# STORAGE.net
KiCad netlist of a schematic drawn in Altium Designer
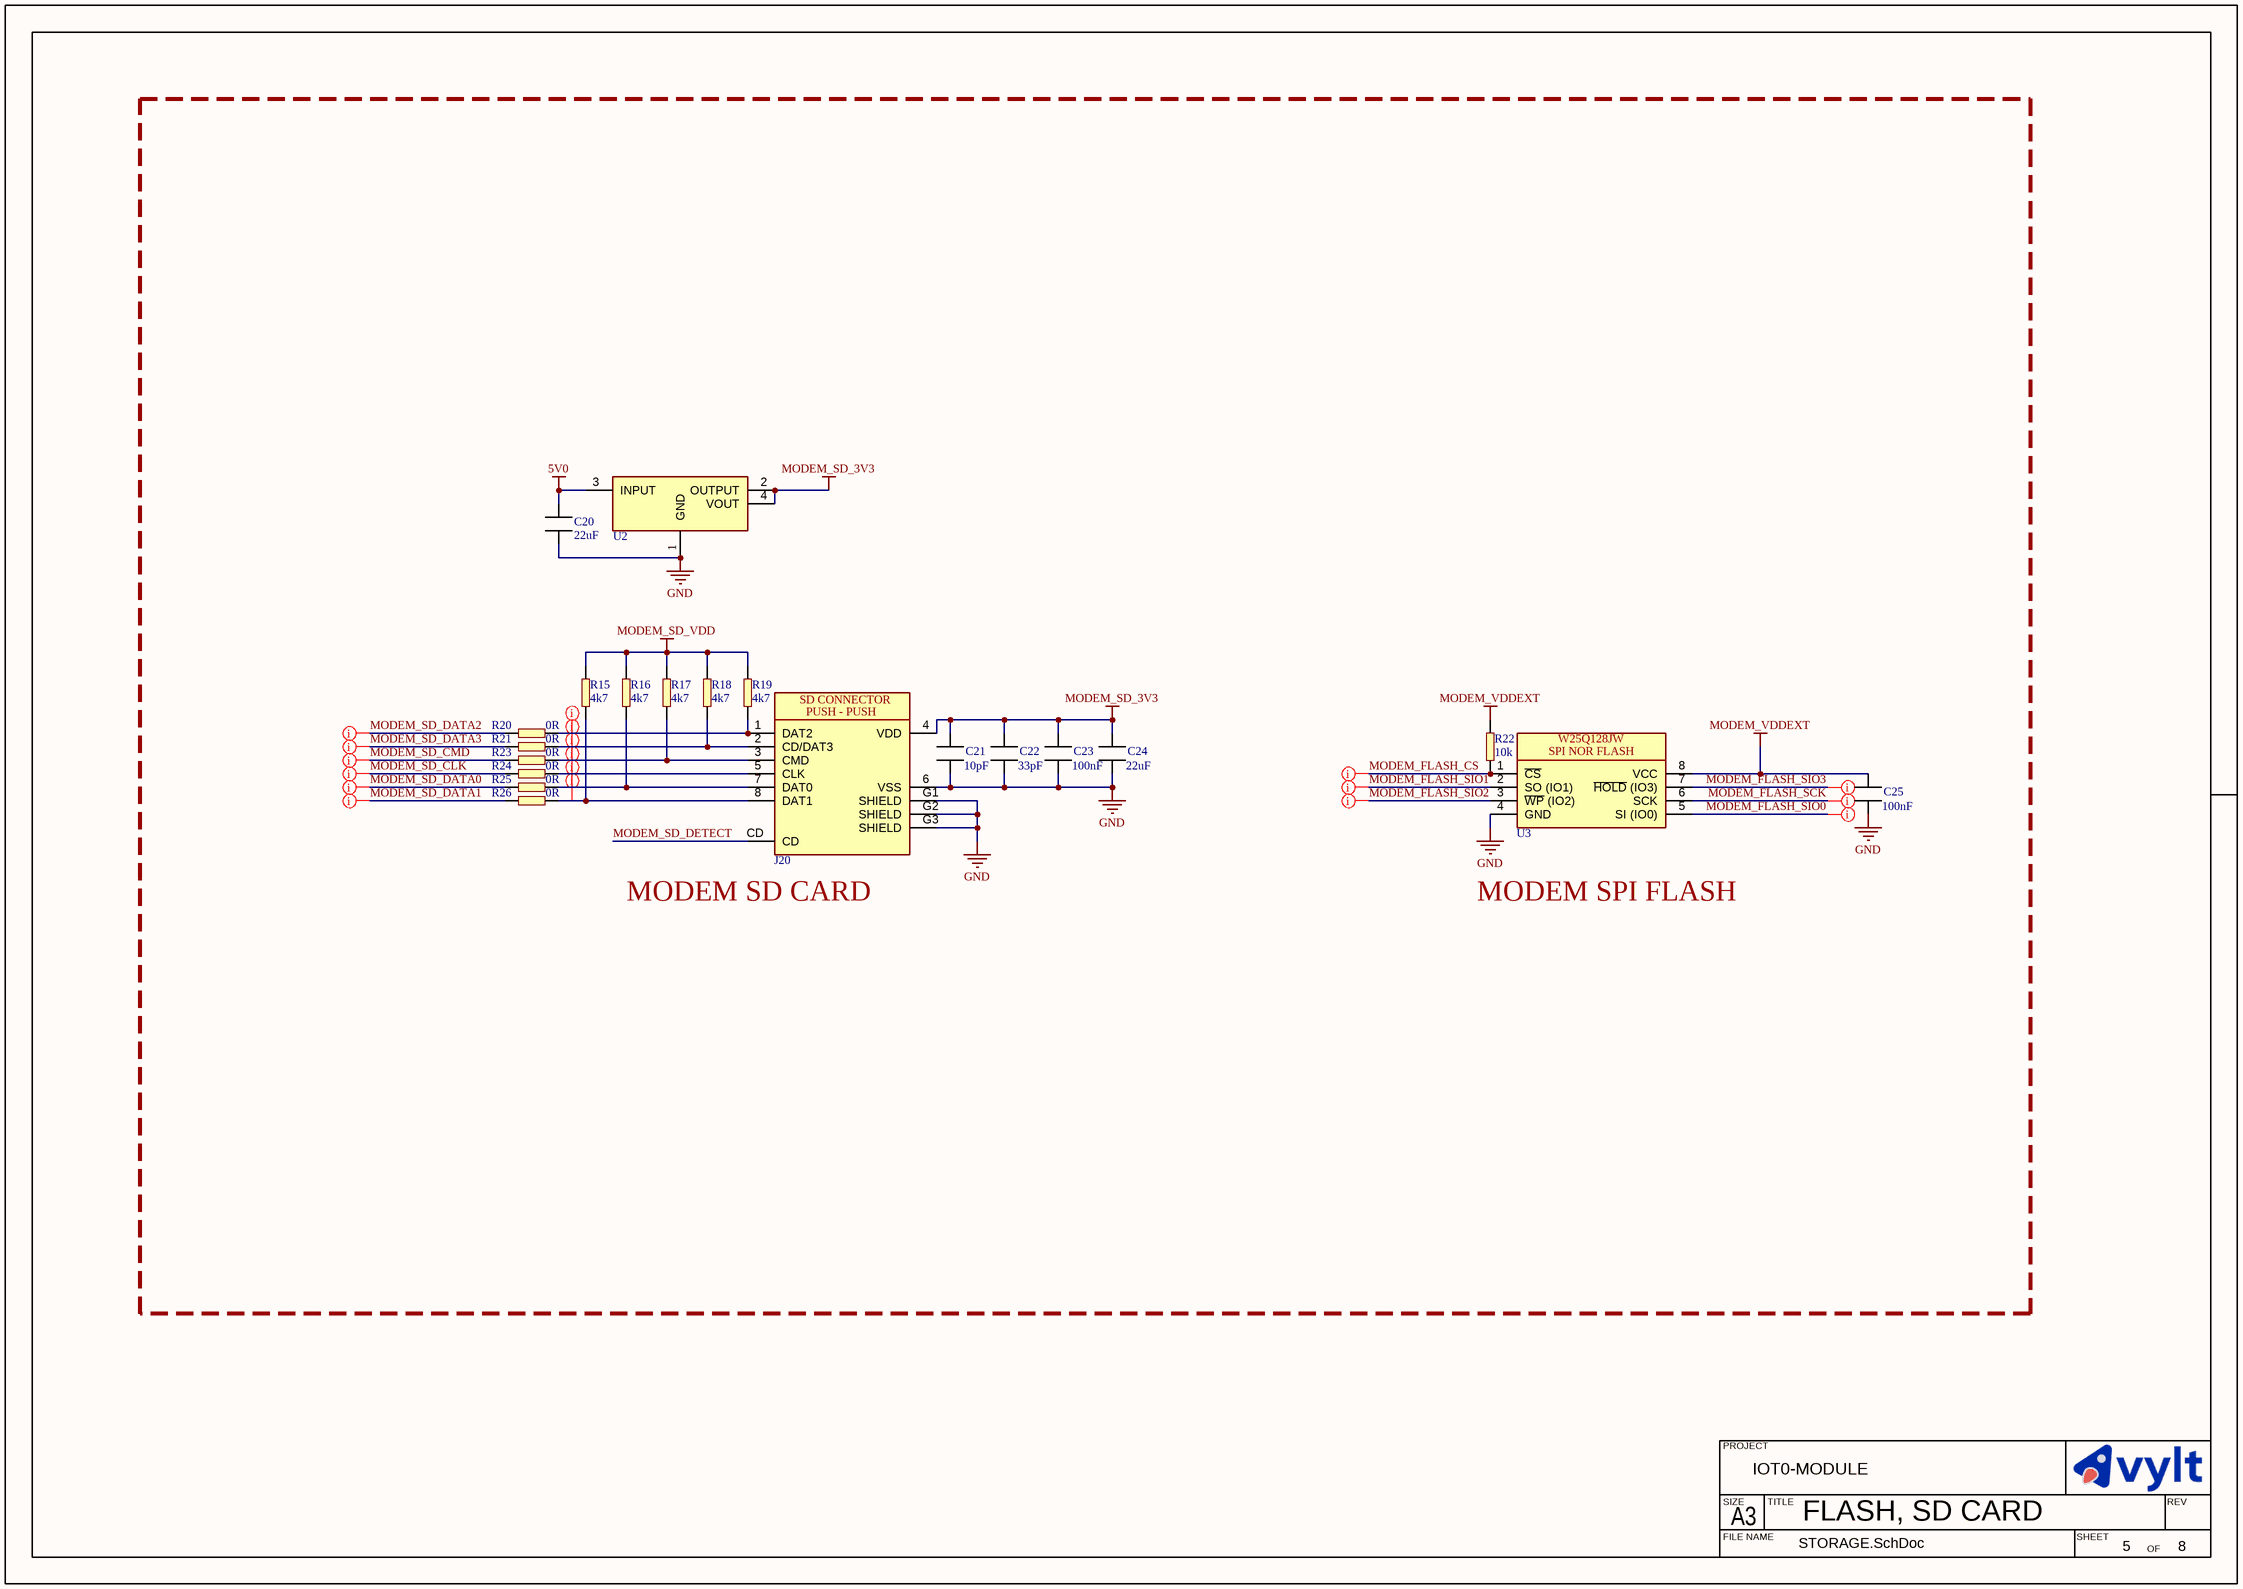
[diagram p0: STORAGE.SchDoc]

(export (version "E")
  (design (tool "Eeschema 10.0.6"))
  (components
    (comp (ref "C20")
      (value "22uF")
      (footprint "CAPC2012X13L")
      (description "Chip Capacitor, 2-Leads, Body 2.00x1.25mm, IPC High Density")
      (fields (field (name "Comment") "MLCC_0805"))
      (libsource (lib "Capacitor") (part "MLCC_0805"))
    )
    (comp (ref "C21")
      (value "10pF")
      (footprint "CAPC2012X13L")
      (description "Chip Capacitor, 2-Leads, Body 2.00x1.25mm, IPC High Density")
      (fields (field (name "Comment") "MLCC_0805"))
      (libsource (lib "Capacitor") (part "MLCC_0805"))
    )
    (comp (ref "C22")
      (value "33pF")
      (footprint "CAPC2012X13L")
      (description "Chip Capacitor, 2-Leads, Body 2.00x1.25mm, IPC High Density")
      (fields (field (name "Comment") "MLCC_0805"))
      (libsource (lib "Capacitor") (part "MLCC_0805"))
    )
    (comp (ref "C23")
      (value "100nF")
      (footprint "CAPC2012X13L")
      (description "Chip Capacitor, 2-Leads, Body 2.00x1.25mm, IPC High Density")
      (fields (field (name "Comment") "MLCC_0805"))
      (libsource (lib "Capacitor") (part "MLCC_0805"))
    )
    (comp (ref "C24")
      (value "22uF")
      (footprint "CAPC2012X13L")
      (description "Chip Capacitor, 2-Leads, Body 2.00x1.25mm, IPC High Density")
      (fields (field (name "Comment") "MLCC_0805"))
      (libsource (lib "Capacitor") (part "MLCC_0805"))
    )
    (comp (ref "C25")
      (value "100nF")
      (footprint "CAPC2012X13L")
      (description "Chip Capacitor, 2-Leads, Body 2.00x1.25mm, IPC High Density")
      (fields (field (name "Comment") "MLCC_0805"))
      (libsource (lib "Capacitor") (part "MLCC_0805"))
    )
    (comp (ref "J20")
      (value "GTFP084")
      (footprint "GTFP084")
      (description "9 (8 + 1) Position Card Connector Secure Digital - microSD™ Surface Mount, Right Angle Gold")
      (libsource (lib "Connectors") (part "GTFP084"))
    )
    (comp (ref "R15")
      (value "4k7")
      (footprint "RES_0603")
      (description "RES_0603")
      (fields (field (name "Comment") "ERP_101-1"))
      (libsource (lib "Resistor") (part "RES_0603"))
    )
    (comp (ref "R16")
      (value "4k7")
      (footprint "RES_0603")
      (description "RES_0603")
      (fields (field (name "Comment") "ERP_101-1"))
      (libsource (lib "Resistor") (part "RES_0603"))
    )
    (comp (ref "R17")
      (value "4k7")
      (footprint "RES_0603")
      (description "RES_0603")
      (fields (field (name "Comment") "ERP_101-1"))
      (libsource (lib "Resistor") (part "RES_0603"))
    )
    (comp (ref "R18")
      (value "4k7")
      (footprint "RES_0603")
      (description "RES_0603")
      (fields (field (name "Comment") "ERP_101-1"))
      (libsource (lib "Resistor") (part "RES_0603"))
    )
    (comp (ref "R19")
      (value "4k7")
      (footprint "RES_0603")
      (description "RES_0603")
      (fields (field (name "Comment") "ERP_101-1"))
      (libsource (lib "Resistor") (part "RES_0603"))
    )
    (comp (ref "R20")
      (value "0R")
      (footprint "RES_0603")
      (description "RES_0603")
      (fields (field (name "Comment") "ERP_101-1"))
      (libsource (lib "") (part "RES_0603_1"))
    )
    (comp (ref "R21")
      (value "0R")
      (footprint "RES_0603")
      (description "RES_0603")
      (fields (field (name "Comment") "ERP_101-1"))
      (libsource (lib "") (part "RES_0603_1"))
    )
    (comp (ref "R22")
      (value "10k")
      (footprint "RES_0603")
      (description "RES_0603")
      (fields (field (name "Comment") "ERP_101-1"))
      (libsource (lib "Resistor") (part "RES_0603"))
    )
    (comp (ref "R23")
      (value "0R")
      (footprint "RES_0603")
      (description "RES_0603")
      (fields (field (name "Comment") "ERP_101-1"))
      (libsource (lib "") (part "RES_0603_1"))
    )
    (comp (ref "R24")
      (value "0R")
      (footprint "RES_0603")
      (description "RES_0603")
      (fields (field (name "Comment") "ERP_101-1"))
      (libsource (lib "") (part "RES_0603_1"))
    )
    (comp (ref "R25")
      (value "0R")
      (footprint "RES_0603")
      (description "RES_0603")
      (fields (field (name "Comment") "ERP_101-1"))
      (libsource (lib "") (part "RES_0603_1"))
    )
    (comp (ref "R26")
      (value "0R")
      (footprint "RES_0603")
      (description "RES_0603")
      (fields (field (name "Comment") "ERP_101-1"))
      (libsource (lib "") (part "RES_0603_1"))
    )
    (comp (ref "U2")
      (value "ERP_123-1")
      (footprint "AMS1117_SOT223")
      (description "AMS1117 LDO")
      (libsource (lib "VoltageRegulator") (part "AMS1117_SOT223"))
    )
    (comp (ref "U3")
      (value "W25Q128JW")
      (footprint "SOIC127P800X216-8L")
      (description "FLASH - NOR Memory IC SPI - Quad I/O 133 MHz 8-SOIC")
      (libsource (lib "FLASH") (part "W25Q128JW"))
    )
  )
  (nets
    (net (code "1") (name "/MODEM_FLASH_CS") (class "Default")
      (node (ref "R22") (pin "1") (pinfunction "1_1") (pintype "passive"))
      (node (ref "U3") (pin "1") (pinfunction "~{CS}_1") (pintype "passive"))
    )
    (net (code "2") (name "/MODEM_FLASH_SCK") (class "Default")
      (node (ref "U3") (pin "6") (pinfunction "SCK_6") (pintype "passive"))
    )
    (net (code "3") (name "/MODEM_FLASH_SIO0") (class "Default")
      (node (ref "U3") (pin "5") (pinfunction "SI_(IO0)_5") (pintype "passive"))
    )
    (net (code "4") (name "/MODEM_FLASH_SIO1") (class "Default")
      (node (ref "U3") (pin "2") (pinfunction "SO_(IO1)_2") (pintype "passive"))
    )
    (net (code "5") (name "/MODEM_FLASH_SIO2") (class "Default")
      (node (ref "U3") (pin "3") (pinfunction "~{WP}_(IO2)_3") (pintype "passive"))
    )
    (net (code "6") (name "/MODEM_FLASH_SIO3") (class "Default")
      (node (ref "U3") (pin "7") (pinfunction "~{HOLD}_(IO3)_7") (pintype "passive"))
    )
    (net (code "7") (name "/MODEM_SD_CLK") (class "Default")
      (node (ref "R24") (pin "2") (pinfunction "2_2") (pintype "passive"))
    )
    (net (code "8") (name "/MODEM_SD_CMD") (class "Default")
      (node (ref "R23") (pin "2") (pinfunction "2_2") (pintype "passive"))
    )
    (net (code "9") (name "/MODEM_SD_DATA0") (class "Default")
      (node (ref "R25") (pin "2") (pinfunction "2_2") (pintype "passive"))
    )
    (net (code "10") (name "/MODEM_SD_DATA1") (class "Default")
      (node (ref "R26") (pin "2") (pinfunction "2_2") (pintype "passive"))
    )
    (net (code "11") (name "/MODEM_SD_DATA2") (class "Default")
      (node (ref "R20") (pin "2") (pinfunction "2_2") (pintype "passive"))
    )
    (net (code "12") (name "/MODEM_SD_DATA3") (class "Default")
      (node (ref "R21") (pin "2") (pinfunction "2_2") (pintype "passive"))
    )
    (net (code "13") (name "/MODEM_SD_DETECT") (class "Default")
      (node (ref "J20") (pin "CD") (pinfunction "CD_CD") (pintype "passive"))
    )
    (net (code "14") (name "5V0") (class "Default")
      (node (ref "C20") (pin "1") (pinfunction "1_1") (pintype "passive"))
      (node (ref "U2") (pin "3") (pinfunction "INPUT_3") (pintype "passive"))
    )
    (net (code "15") (name "GND") (class "Default")
      (node (ref "C20") (pin "2") (pinfunction "2_2") (pintype "passive"))
      (node (ref "C21") (pin "2") (pinfunction "2_2") (pintype "passive"))
      (node (ref "C22") (pin "2") (pinfunction "2_2") (pintype "passive"))
      (node (ref "C23") (pin "2") (pinfunction "2_2") (pintype "passive"))
      (node (ref "C24") (pin "2") (pinfunction "2_2") (pintype "passive"))
      (node (ref "C25") (pin "2") (pinfunction "2_2") (pintype "passive"))
      (node (ref "J20") (pin "6") (pinfunction "VSS_6") (pintype "power_in"))
      (node (ref "J20") (pin "G1") (pinfunction "SHIELD_G1") (pintype "power_in"))
      (node (ref "J20") (pin "G2") (pinfunction "SHIELD_G2") (pintype "power_in"))
      (node (ref "J20") (pin "G3") (pinfunction "SHIELD_G3") (pintype "power_in"))
      (node (ref "U2") (pin "1") (pinfunction "GND_1") (pintype "power_in"))
      (node (ref "U3") (pin "4") (pinfunction "GND_4") (pintype "passive"))
    )
    (net (code "16") (name "MODEM_SD_3V3") (class "Default")
      (node (ref "C21") (pin "1") (pinfunction "1_1") (pintype "passive"))
      (node (ref "C22") (pin "1") (pinfunction "1_1") (pintype "passive"))
      (node (ref "C23") (pin "1") (pinfunction "1_1") (pintype "passive"))
      (node (ref "C24") (pin "1") (pinfunction "1_1") (pintype "passive"))
      (node (ref "J20") (pin "4") (pinfunction "VDD_4") (pintype "passive"))
      (node (ref "U2") (pin "2") (pinfunction "OUTPUT_2") (pintype "passive"))
      (node (ref "U2") (pin "4") (pinfunction "VOUT_4") (pintype "passive"))
    )
    (net (code "17") (name "MODEM_SD_VDD") (class "Default")
      (node (ref "R15") (pin "2") (pinfunction "2_2") (pintype "passive"))
      (node (ref "R16") (pin "2") (pinfunction "2_2") (pintype "passive"))
      (node (ref "R17") (pin "2") (pinfunction "2_2") (pintype "passive"))
      (node (ref "R18") (pin "2") (pinfunction "2_2") (pintype "passive"))
      (node (ref "R19") (pin "2") (pinfunction "2_2") (pintype "passive"))
    )
    (net (code "18") (name "MODEM_VDDEXT") (class "Default")
      (node (ref "C25") (pin "1") (pinfunction "1_1") (pintype "passive"))
      (node (ref "R22") (pin "2") (pinfunction "2_2") (pintype "passive"))
      (node (ref "U3") (pin "8") (pinfunction "VCC_8") (pintype "passive"))
    )
    (net (code "19") (name "Net-(J20-CD{slash}DAT3)") (class "Default")
      (node (ref "J20") (pin "2") (pinfunction "CD/DAT3_2") (pintype "passive"))
      (node (ref "R18") (pin "1") (pinfunction "1_1") (pintype "passive"))
      (node (ref "R21") (pin "1") (pinfunction "1_1") (pintype "passive"))
    )
    (net (code "20") (name "Net-(J20-CLK)") (class "Default")
      (node (ref "J20") (pin "5") (pinfunction "CLK_5") (pintype "passive"))
      (node (ref "R24") (pin "1") (pinfunction "1_1") (pintype "passive"))
    )
    (net (code "21") (name "Net-(J20-CMD)") (class "Default")
      (node (ref "J20") (pin "3") (pinfunction "CMD_3") (pintype "passive"))
      (node (ref "R17") (pin "1") (pinfunction "1_1") (pintype "passive"))
      (node (ref "R23") (pin "1") (pinfunction "1_1") (pintype "passive"))
    )
    (net (code "22") (name "Net-(J20-DAT0)") (class "Default")
      (node (ref "J20") (pin "7") (pinfunction "DAT0_7") (pintype "passive"))
      (node (ref "R16") (pin "1") (pinfunction "1_1") (pintype "passive"))
      (node (ref "R25") (pin "1") (pinfunction "1_1") (pintype "passive"))
    )
    (net (code "23") (name "Net-(J20-DAT1)") (class "Default")
      (node (ref "J20") (pin "8") (pinfunction "DAT1_8") (pintype "passive"))
      (node (ref "R15") (pin "1") (pinfunction "1_1") (pintype "passive"))
      (node (ref "R26") (pin "1") (pinfunction "1_1") (pintype "passive"))
    )
    (net (code "24") (name "Net-(J20-DAT2)") (class "Default")
      (node (ref "J20") (pin "1") (pinfunction "DAT2_1") (pintype "passive"))
      (node (ref "R19") (pin "1") (pinfunction "1_1") (pintype "passive"))
      (node (ref "R20") (pin "1") (pinfunction "1_1") (pintype "passive"))
    )
  )
)
